# power.net
KiCad netlist of a schematic drawn in Altium Designer
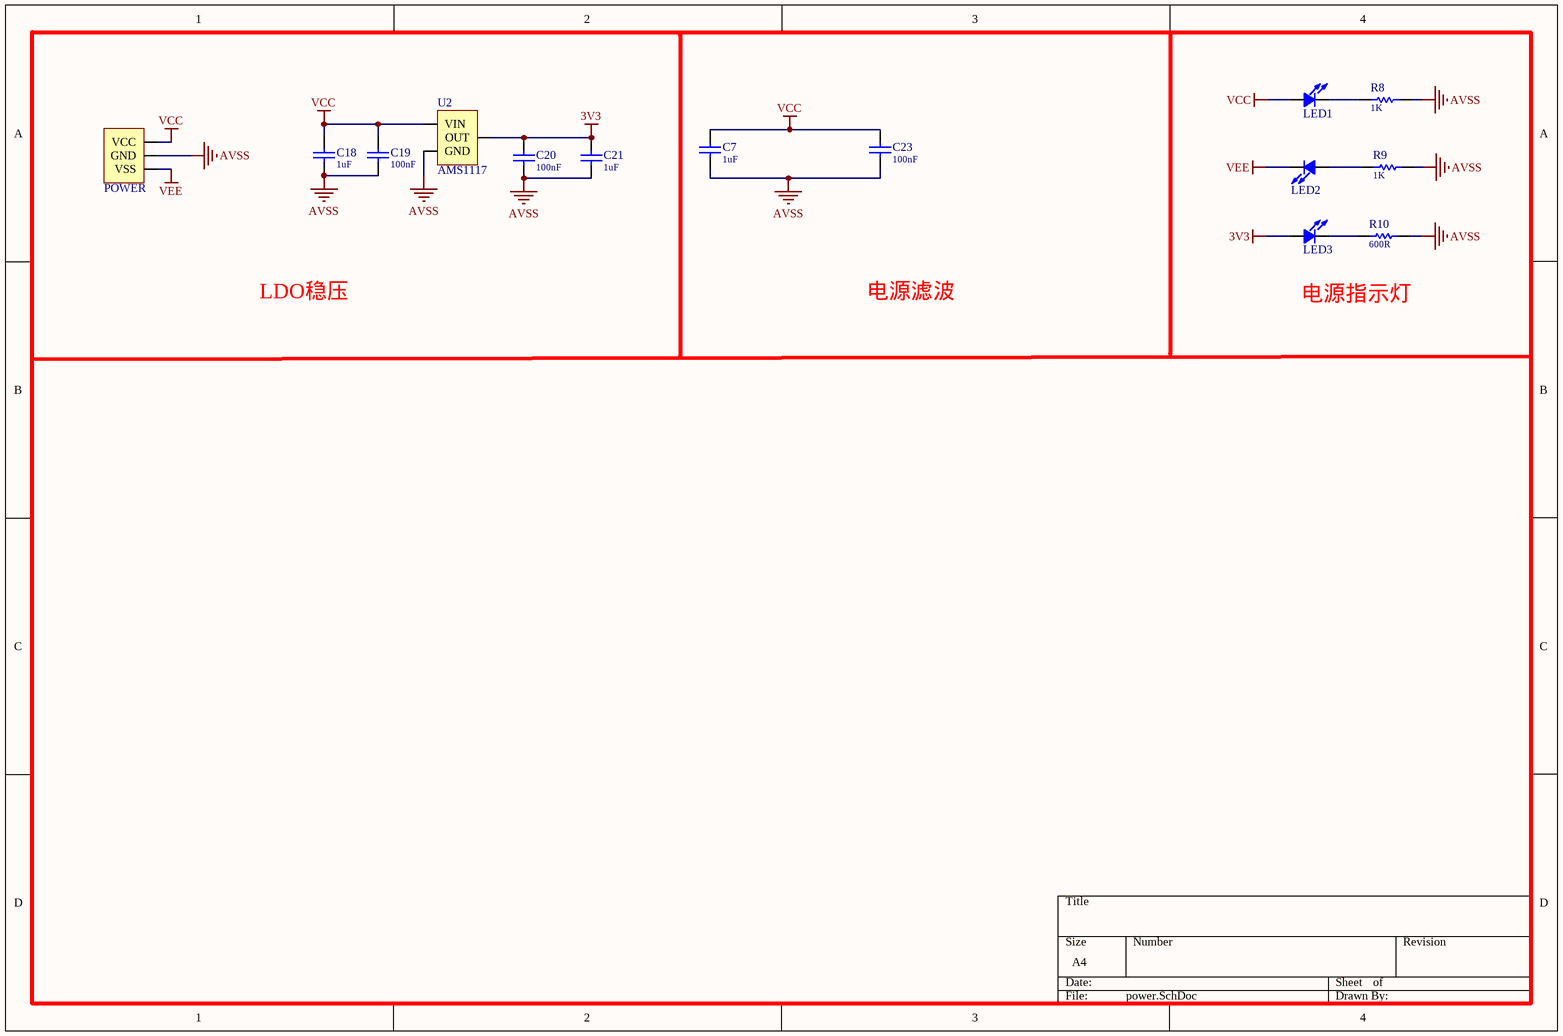
[diagram p0: power.SchDoc]

(export (version "E")
  (design (tool "Eeschema 10.0.6"))
  (components
    (comp (ref "C7")
      (value "1uF")
      (footprint "C0603-L")
      (description "贴片瓷片电容")
      (fields (field (name "Comment") "Cap-S"))
      (libsource (lib "XuZhe") (part "Cap-S"))
    )
    (comp (ref "C18")
      (value "1uF")
      (footprint "C0603-L")
      (description "贴片瓷片电容")
      (fields (field (name "Comment") "Cap-S"))
      (libsource (lib "XuZhe") (part "Cap-S"))
    )
    (comp (ref "C19")
      (value "100nF")
      (footprint "C0603-L")
      (description "贴片瓷片电容")
      (fields (field (name "Comment") "Cap-S"))
      (libsource (lib "XuZhe") (part "Cap-S"))
    )
    (comp (ref "C20")
      (value "100nF")
      (footprint "C0603-L")
      (description "贴片瓷片电容")
      (fields (field (name "Comment") "Cap-S"))
      (libsource (lib "XuZhe") (part "Cap-S"))
    )
    (comp (ref "C21")
      (value "1uF")
      (footprint "C0603-L")
      (description "贴片瓷片电容")
      (fields (field (name "Comment") "Cap-S"))
      (libsource (lib "XuZhe") (part "Cap-S"))
    )
    (comp (ref "C23")
      (value "100nF")
      (footprint "C0603-L")
      (description "贴片瓷片电容")
      (fields (field (name "Comment") "Cap-S"))
      (libsource (lib "XuZhe") (part "Cap-S"))
    )
    (comp (ref "LED1")
      (value "LED")
      (footprint "Led-0805_L")
      (description "发光二极管")
      (libsource (lib "XuZhe") (part "LED"))
    )
    (comp (ref "LED2")
      (value "LED")
      (footprint "Led-0805_L")
      (description "发光二极管")
      (libsource (lib "XuZhe") (part "LED"))
    )
    (comp (ref "LED3")
      (value "LED")
      (footprint "Led-0805_L")
      (description "发光二极管")
      (libsource (lib "XuZhe") (part "LED"))
    )
    (comp (ref "POWER")
      (value "Power-3P")
      (footprint "SIPA03")
      (description "供电端子")
      (libsource (lib "XuZhe") (part "Power-3P"))
    )
    (comp (ref "R8")
      (value "1K")
      (footprint "R0603-L")
      (description "贴片电阻")
      (fields (field (name "Comment") "R"))
      (libsource (lib "XuZhe") (part "Res"))
    )
    (comp (ref "R9")
      (value "1K")
      (footprint "R0603-L")
      (description "贴片电阻")
      (fields (field (name "Comment") "R"))
      (libsource (lib "XuZhe") (part "Res"))
    )
    (comp (ref "R10")
      (value "600R")
      (footprint "R0603-L")
      (description "贴片电阻")
      (fields (field (name "Comment") "R"))
      (libsource (lib "XuZhe") (part "Res"))
    )
    (comp (ref "U2") (value "AMS1117") (footprint "SOT-223") (libsource (lib "XuZhe") (part "AMS1117")))
  )
  (nets
    (net (code "1") (name "3V3") (class "Default")
      (node (ref "C20") (pin "2") (pinfunction "2_2") (pintype "passive"))
      (node (ref "C21") (pin "2") (pinfunction "2_2") (pintype "passive"))
      (node (ref "LED3") (pin "1") (pinfunction "1_1") (pintype "passive"))
      (node (ref "U2") (pin "2") (pinfunction "OUT_2") (pintype "passive"))
    )
    (net (code "2") (name "AVSS") (class "Default")
      (node (ref "C18") (pin "1") (pinfunction "1_1") (pintype "passive"))
      (node (ref "C19") (pin "1") (pinfunction "1_1") (pintype "passive"))
      (node (ref "C20") (pin "1") (pinfunction "1_1") (pintype "passive"))
      (node (ref "C21") (pin "1") (pinfunction "1_1") (pintype "passive"))
      (node (ref "C23") (pin "2") (pinfunction "2_2") (pintype "passive"))
      (node (ref "C7") (pin "2") (pinfunction "2_2") (pintype "passive"))
      (node (ref "POWER") (pin "2") (pinfunction "GND_2") (pintype "passive"))
      (node (ref "R10") (pin "2") (pinfunction "2_2") (pintype "passive"))
      (node (ref "R8") (pin "2") (pinfunction "2_2") (pintype "passive"))
      (node (ref "R9") (pin "2") (pinfunction "2_2") (pintype "passive"))
      (node (ref "U2") (pin "1") (pinfunction "GND_1") (pintype "passive"))
    )
    (net (code "3") (name "Net-(LED1-Pad2)") (class "Default")
      (node (ref "LED1") (pin "2") (pinfunction "2_2") (pintype "passive"))
      (node (ref "R8") (pin "1") (pinfunction "1_1") (pintype "passive"))
    )
    (net (code "4") (name "Net-(LED2-Pad1)") (class "Default")
      (node (ref "LED2") (pin "1") (pinfunction "1_1") (pintype "passive"))
      (node (ref "R9") (pin "1") (pinfunction "1_1") (pintype "passive"))
    )
    (net (code "5") (name "Net-(LED3-Pad2)") (class "Default")
      (node (ref "LED3") (pin "2") (pinfunction "2_2") (pintype "passive"))
      (node (ref "R10") (pin "1") (pinfunction "1_1") (pintype "passive"))
    )
    (net (code "6") (name "VCC") (class "Default")
      (node (ref "C18") (pin "2") (pinfunction "2_2") (pintype "passive"))
      (node (ref "C19") (pin "2") (pinfunction "2_2") (pintype "passive"))
      (node (ref "C23") (pin "1") (pinfunction "1_1") (pintype "passive"))
      (node (ref "C7") (pin "1") (pinfunction "1_1") (pintype "passive"))
      (node (ref "LED1") (pin "1") (pinfunction "1_1") (pintype "passive"))
      (node (ref "POWER") (pin "1") (pinfunction "VCC_1") (pintype "passive"))
      (node (ref "U2") (pin "3") (pinfunction "VIN_3") (pintype "passive"))
    )
    (net (code "7") (name "VEE") (class "Default")
      (node (ref "LED2") (pin "2") (pinfunction "2_2") (pintype "passive"))
      (node (ref "POWER") (pin "3") (pinfunction "VSS_3") (pintype "passive"))
    )
  )
)
